# Memory.net
KiCad netlist of a schematic drawn in Altium Designer
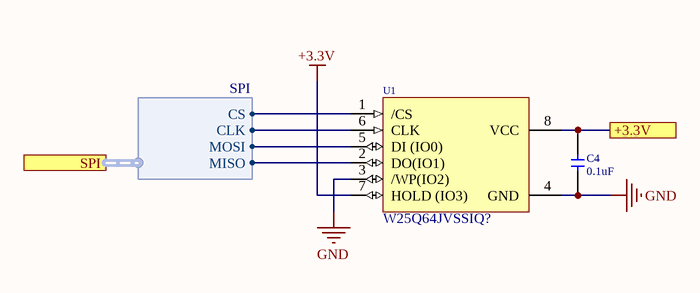
[diagram p0: Memory.SchDoc]

(export (version "E")
  (design (tool "Eeschema 10.0.6"))
  (components
    (comp (ref "C4")
      (value "0.1uF")
      (footprint "CERCAP 0402")
      (description "Capacitor")
      (fields (field (name "Comment") "CERCAP 0402 0.1uF * X7R"))
      (libsource (lib "!main") (part "!Capacitor"))
    )
    (comp (ref "U1") (value "W25Q64JVSSIQ?") (footprint "SO-8") (libsource (lib "memory") (part "Flash")))
  )
  (nets
    (net (code "2") (name "+3.3V") (class "Default")
      (node (ref "C4") (pin "2") (pintype "passive"))
      (node (ref "U1") (pin "7") (pinfunction "HOLD_(IO3)_7") (pintype "bidirectional"))
      (node (ref "U1") (pin "8") (pinfunction "VCC_8") (pintype "power_in"))
    )
    (net (code "3") (name "/CLK") (class "Default")
      (node (ref "U1") (pin "6") (pinfunction "CLK_6") (pintype "input"))
    )
    (net (code "4") (name "/CS") (class "Default")
      (node (ref "U1") (pin "1") (pinfunction "/CS_1") (pintype "input"))
    )
    (net (code "5") (name "/MISO") (class "Default")
      (node (ref "U1") (pin "2") (pinfunction "DO(IO1)_2") (pintype "bidirectional"))
    )
    (net (code "6") (name "/MOSI") (class "Default")
      (node (ref "U1") (pin "5") (pinfunction "DI_(IO0)_5") (pintype "bidirectional"))
    )
    (net (code "8") (name "GND") (class "Default")
      (node (ref "C4") (pin "1") (pintype "passive"))
      (node (ref "U1") (pin "3") (pinfunction "/WP(IO2)_3") (pintype "bidirectional"))
      (node (ref "U1") (pin "4") (pinfunction "GND_4") (pintype "power_in"))
    )
  )
)
